# Tape.net
KiCad netlist of a schematic drawn in Altium Designer
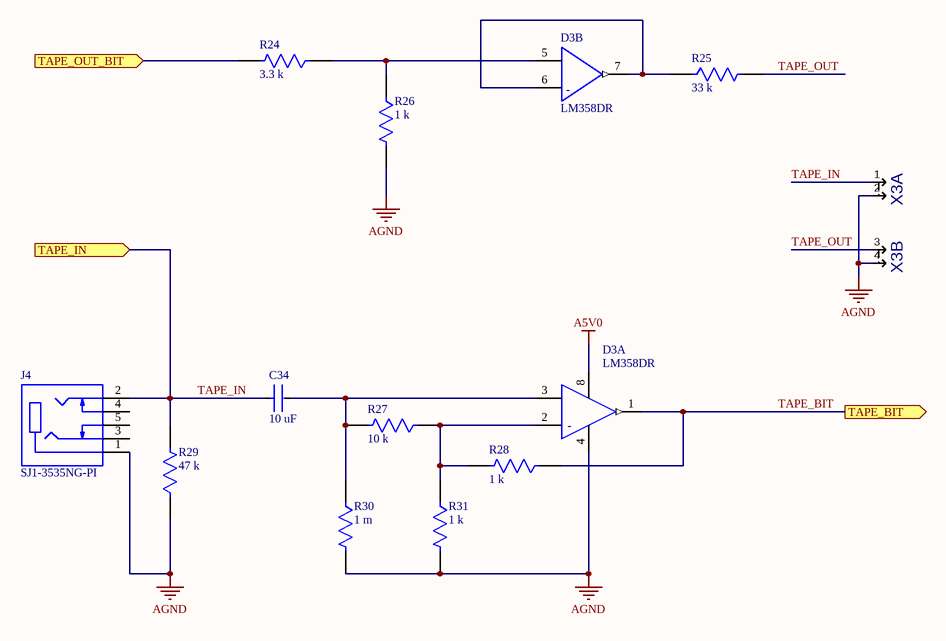
[diagram p0: Tape.SchDoc]

(export (version "E")
  (design (tool "Eeschema 10.0.6"))
  (components
    (comp (ref "C34")
      (value "CC0805-1.5pF")
      (footprint "CC0805")
      (description "CL21 Series 0805 1.5pF 50V ±0.25pF Tolerance C0G Multilayer Ceramic Chip Capacitor")
      (fields
        (field (name "MANUFACTURER PART NUMBER") "CL21C1R5CBANNNC")
        (field (name "MANUFACTURER") "Samsung")
        (field (name "CAPACITANCE") "10 uF")
      )
      (libsource (lib "zxevo") (part "CC0805"))
    )
    (comp (ref "D3")
      (value "LM358DR")
      (footprint "FP-D0008A-MFG")
      (description "IC OPAMP GP 2 CIRCUIT 8SOIC")
      (fields (field (name "MANUFACTURER") "Texas Instruments"))
      (libsource (lib "zxevo") (part "LM358DR"))
    )
    (comp (ref "J4")
      (value "SJ1-3535NG-PI")
      (footprint "CUI_SJ1-3535NG-PI")
      (description "3.5 mm Right-Angle Stereo Jack, 5 pin PCB PCB Mount, Isolated Ground, Pink")
      (fields (field (name "MF") "{'manufacturer': u'CUI'}"))
      (libsource (lib "zxevo") (part "SJ1-3535NG-PI"))
    )
    (comp (ref "R24")
      (value "CR0805-51")
      (footprint "CR0805")
      (description "51Ω ±0.5% 0.1W 1/10W Chip Resistor 0805 (2012 Metric) Thin Film")
      (fields
        (field (name "MANUFACTURER PART NUMBER") "RR1220Q-510-D")
        (field (name "MANUFACTURER") "Susumu")
        (field (name "RESISTANCE") "3.3 k")
      )
      (libsource (lib "zxevo") (part "CR0805"))
    )
    (comp (ref "R25")
      (value "CR0805-51")
      (footprint "CR0805")
      (description "51Ω ±0.5% 0.1W 1/10W Chip Resistor 0805 (2012 Metric) Thin Film")
      (fields
        (field (name "RESISTANCE") "33 k")
        (field (name "MANUFACTURER") "Susumu")
        (field (name "MANUFACTURER PART NUMBER") "RR1220Q-510-D")
      )
      (libsource (lib "zxevo") (part "CR0805"))
    )
    (comp (ref "R26")
      (value "CR0805-51")
      (footprint "CR0805")
      (description "51Ω ±0.5% 0.1W 1/10W Chip Resistor 0805 (2012 Metric) Thin Film")
      (fields
        (field (name "RESISTANCE") "1 k")
        (field (name "MANUFACTURER") "Susumu")
        (field (name "MANUFACTURER PART NUMBER") "RR1220Q-510-D")
      )
      (libsource (lib "zxevo") (part "CR0805"))
    )
    (comp (ref "R27")
      (value "CR0805-51")
      (footprint "CR0805")
      (description "51Ω ±0.5% 0.1W 1/10W Chip Resistor 0805 (2012 Metric) Thin Film")
      (fields
        (field (name "RESISTANCE") "10 k")
        (field (name "MANUFACTURER") "Susumu")
        (field (name "MANUFACTURER PART NUMBER") "RR1220Q-510-D")
      )
      (libsource (lib "zxevo") (part "CR0805"))
    )
    (comp (ref "R28")
      (value "CR0805-51")
      (footprint "CR0805")
      (description "51Ω ±0.5% 0.1W 1/10W Chip Resistor 0805 (2012 Metric) Thin Film")
      (fields
        (field (name "RESISTANCE") "1 k")
        (field (name "MANUFACTURER") "Susumu")
        (field (name "MANUFACTURER PART NUMBER") "RR1220Q-510-D")
      )
      (libsource (lib "zxevo") (part "CR0805"))
    )
    (comp (ref "R29")
      (value "CR0805-51")
      (footprint "CR0805")
      (description "51Ω ±0.5% 0.1W 1/10W Chip Resistor 0805 (2012 Metric) Thin Film")
      (fields
        (field (name "RESISTANCE") "47 k")
        (field (name "MANUFACTURER") "Susumu")
        (field (name "MANUFACTURER PART NUMBER") "RR1220Q-510-D")
      )
      (libsource (lib "zxevo") (part "CR0805"))
    )
    (comp (ref "R30")
      (value "CR0805-51")
      (footprint "CR0805")
      (description "51Ω ±0.5% 0.1W 1/10W Chip Resistor 0805 (2012 Metric) Thin Film")
      (fields
        (field (name "RESISTANCE") "1 m")
        (field (name "MANUFACTURER") "Susumu")
        (field (name "MANUFACTURER PART NUMBER") "RR1220Q-510-D")
      )
      (libsource (lib "zxevo") (part "CR0805"))
    )
    (comp (ref "R31")
      (value "CR0805-51")
      (footprint "CR0805")
      (description "51Ω ±0.5% 0.1W 1/10W Chip Resistor 0805 (2012 Metric) Thin Film")
      (fields
        (field (name "RESISTANCE") "1 k")
        (field (name "MANUFACTURER") "Susumu")
        (field (name "MANUFACTURER PART NUMBER") "RR1220Q-510-D")
      )
      (libsource (lib "zxevo") (part "CR0805"))
    )
    (comp (ref "X3") (value "PLB2-2") (footprint "PLB2-2") (libsource (lib "zxevo") (part "PLB2-2")))
  )
  (nets
    (net (code "1") (name "/TAPE_BIT") (class "Default")
      (node (ref "D3") (pin "1") (pinfunction "1OUT_1") (pintype "output"))
      (node (ref "R28") (pin "1") (pinfunction "1_1") (pintype "passive"))
    )
    (net (code "2") (name "/TAPE_IN") (class "Default")
      (node (ref "C34") (pin "1") (pinfunction "1_1") (pintype "passive"))
      (node (ref "J4") (pin "2") (pinfunction "2_2") (pintype "passive"))
      (node (ref "R29") (pin "2") (pinfunction "2_2") (pintype "passive"))
      (node (ref "X3") (pin "1") (pinfunction "1_1") (pintype "passive"))
    )
    (net (code "3") (name "/TAPE_OUT") (class "Default")
      (node (ref "R25") (pin "2") (pinfunction "2_2") (pintype "passive"))
      (node (ref "X3") (pin "3") (pinfunction "1_3") (pintype "passive"))
    )
    (net (code "4") (name "/TAPE_OUT_BIT") (class "Default")
      (node (ref "R24") (pin "2") (pinfunction "2_2") (pintype "passive"))
    )
    (net (code "5") (name "A5V0") (class "Default")
      (node (ref "D3") (pin "8") (pinfunction "V+_8") (pintype "power_in"))
    )
    (net (code "6") (name "AGND") (class "Default")
      (node (ref "D3") (pin "4") (pinfunction "V-_4") (pintype "power_in"))
      (node (ref "J4") (pin "1") (pinfunction "1_1") (pintype "passive"))
      (node (ref "R26") (pin "2") (pinfunction "2_2") (pintype "passive"))
      (node (ref "R29") (pin "1") (pinfunction "1_1") (pintype "passive"))
      (node (ref "R30") (pin "2") (pinfunction "2_2") (pintype "passive"))
      (node (ref "R31") (pin "2") (pinfunction "2_2") (pintype "passive"))
      (node (ref "X3") (pin "2") (pinfunction "2_2") (pintype "passive"))
      (node (ref "X3") (pin "4") (pinfunction "2_4") (pintype "passive"))
    )
    (net (code "7") (name "Net-(D3A-IN1+)") (class "Default")
      (node (ref "C34") (pin "2") (pinfunction "2_2") (pintype "passive"))
      (node (ref "D3") (pin "3") (pinfunction "IN1+_3") (pintype "tri_state"))
      (node (ref "R27") (pin "2") (pinfunction "2_2") (pintype "passive"))
      (node (ref "R30") (pin "1") (pinfunction "1_1") (pintype "passive"))
    )
    (net (code "8") (name "Net-(D3A-IN1-)") (class "Default")
      (node (ref "D3") (pin "2") (pinfunction "IN1-_2") (pintype "tri_state"))
      (node (ref "R27") (pin "1") (pinfunction "1_1") (pintype "passive"))
      (node (ref "R28") (pin "2") (pinfunction "2_2") (pintype "passive"))
      (node (ref "R31") (pin "1") (pinfunction "1_1") (pintype "passive"))
    )
    (net (code "9") (name "Net-(D3B-2OUT)") (class "Default")
      (node (ref "D3") (pin "6") (pinfunction "IN2-_6") (pintype "tri_state"))
      (node (ref "D3") (pin "7") (pinfunction "2OUT_7") (pintype "output"))
      (node (ref "R25") (pin "1") (pinfunction "1_1") (pintype "passive"))
    )
    (net (code "10") (name "Net-(D3B-IN2+)") (class "Default")
      (node (ref "D3") (pin "5") (pinfunction "IN2+_5") (pintype "tri_state"))
      (node (ref "R24") (pin "1") (pinfunction "1_1") (pintype "passive"))
      (node (ref "R26") (pin "1") (pinfunction "1_1") (pintype "passive"))
    )
    (net (code "11") (name "unconnected-(J4-Pad3)") (class "Default")
      (node (ref "J4") (pin "3") (pinfunction "3_3") (pintype "passive"))
    )
    (net (code "12") (name "unconnected-(J4-Pad4)") (class "Default")
      (node (ref "J4") (pin "4") (pinfunction "4_4") (pintype "passive"))
    )
    (net (code "13") (name "unconnected-(J4-Pad5)") (class "Default")
      (node (ref "J4") (pin "5") (pinfunction "5_5") (pintype "passive"))
    )
  )
)
